# Protoshield_V1_0.net
KiCad netlist of a schematic drawn in EAGLE
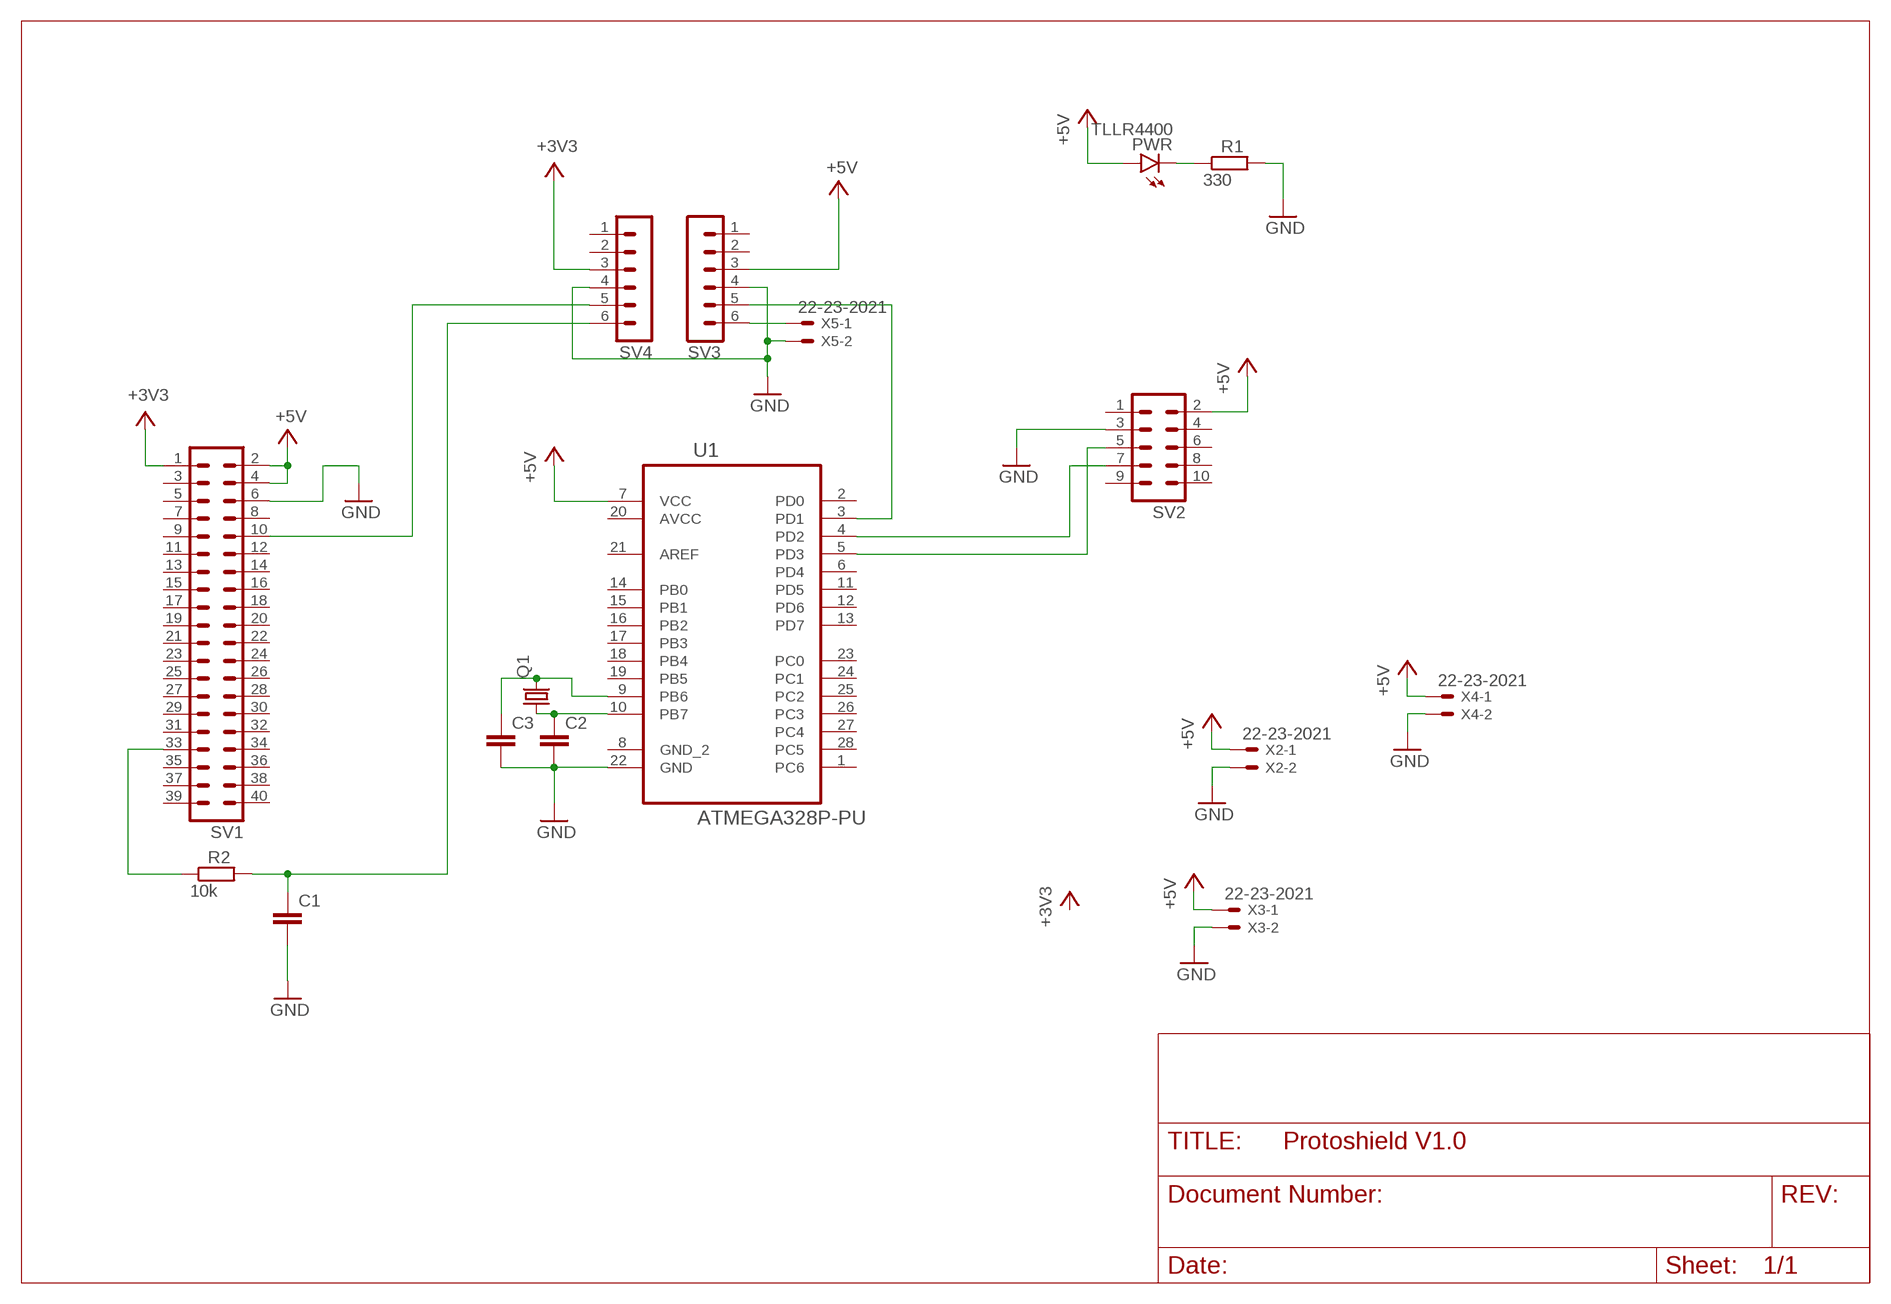
[diagram p0: schematic, sheet 1]

(export (version "E")
  (design (tool "Eeschema 10.0.6"))
  (components
    (comp (ref "C1")
      (value "C-EU050-024X044")
      (footprint "eagle-import:C050-024X044")
      (libsource (lib "eagle-import") (part "C-EU050-024X044"))
    )
    (comp (ref "C2")
      (value "C-EU050-024X044")
      (footprint "eagle-import:C050-024X044")
      (libsource (lib "eagle-import") (part "C-EU050-024X044"))
    )
    (comp (ref "C3")
      (value "C-EU050-024X044")
      (footprint "eagle-import:C050-024X044")
      (libsource (lib "eagle-import") (part "C-EU050-024X044"))
    )
    (comp (ref "PWR")
      (value "TLLR4400")
      (footprint "eagle-import:LED3MM")
      (fields (field (name "MF") "VISHAY SEMICONDUCTOR"))
      (libsource (lib "eagle-import") (part "TLLR4400"))
    )
    (comp (ref "Q1")
      (value "CRYSTALHC49S")
      (footprint "eagle-import:HC49_S")
      (libsource (lib "eagle-import") (part "CRYSTALHC49S"))
    )
    (comp (ref "R1")
      (value "330")
      (footprint "eagle-import:0207_7")
      (libsource (lib "eagle-import") (part "R-EU_0207/7"))
    )
    (comp (ref "R2")
      (value "10k")
      (footprint "eagle-import:0207_7")
      (libsource (lib "eagle-import") (part "R-EU_0207/7"))
    )
    (comp (ref "SV1")
      (value "MA20-2")
      (footprint "eagle-import:MA20-2")
      (libsource (lib "eagle-import") (part "MA20-2"))
    )
    (comp (ref "SV2")
      (value "MA05-2")
      (footprint "eagle-import:MA05-2")
      (libsource (lib "eagle-import") (part "MA05-2"))
    )
    (comp (ref "SV3")
      (value "MA06-1")
      (footprint "eagle-import:MA06-1")
      (libsource (lib "eagle-import") (part "MA06-1"))
    )
    (comp (ref "SV4")
      (value "MA06-1")
      (footprint "eagle-import:MA06-1")
      (libsource (lib "eagle-import") (part "MA06-1"))
    )
    (comp (ref "U1")
      (value "ATMEGA328P-PU")
      (footprint "eagle-import:DIP254P762X457-28")
      (libsource (lib "eagle-import") (part "ATMEGA328P-PU"))
    )
    (comp (ref "X2")
      (value "22-23-2021")
      (footprint "eagle-import:22-23-2021")
      (fields (field (name "MF") "MOLEX"))
      (libsource (lib "eagle-import") (part "22-23-2021"))
    )
    (comp (ref "X3")
      (value "22-23-2021")
      (footprint "eagle-import:22-23-2021")
      (fields (field (name "MF") "MOLEX"))
      (libsource (lib "eagle-import") (part "22-23-2021"))
    )
    (comp (ref "X4")
      (value "22-23-2021")
      (footprint "eagle-import:22-23-2021")
      (fields (field (name "MF") "MOLEX"))
      (libsource (lib "eagle-import") (part "22-23-2021"))
    )
    (comp (ref "X5")
      (value "22-23-2021")
      (footprint "eagle-import:22-23-2021")
      (fields (field (name "MF") "MOLEX"))
      (libsource (lib "eagle-import") (part "22-23-2021"))
    )
  )
  (nets
    (net (code "1") (name "+3V3") (class "Default")
      (node (ref "SV1") (pin "1") (pinfunction "1_1") (pintype "passive"))
      (node (ref "SV4") (pin "3") (pinfunction "3_3") (pintype "passive"))
    )
    (net (code "2") (name "+5V") (class "Default")
      (node (ref "PWR") (pin "A") (pinfunction "A_A") (pintype "passive"))
      (node (ref "SV1") (pin "2") (pinfunction "2_2") (pintype "passive"))
      (node (ref "SV1") (pin "4") (pinfunction "4_4") (pintype "passive"))
      (node (ref "SV2") (pin "2") (pinfunction "2_2") (pintype "passive"))
      (node (ref "SV3") (pin "3") (pinfunction "3_3") (pintype "passive"))
      (node (ref "U1") (pin "7") (pinfunction "VCC_7") (pintype "power_in"))
      (node (ref "X2") (pin "1") (pinfunction "S_1") (pintype "passive"))
      (node (ref "X3") (pin "1") (pinfunction "S_1") (pintype "passive"))
      (node (ref "X4") (pin "1") (pinfunction "S_1") (pintype "passive"))
    )
    (net (code "3") (name "/AVCC") (class "Default")
      (node (ref "U1") (pin "20") (pinfunction "AVCC_20") (pintype "power_in"))
    )
    (net (code "4") (name "GND") (class "Default")
      (node (ref "C1") (pin "2") (pinfunction "2_2") (pintype "passive"))
      (node (ref "C2") (pin "2") (pinfunction "2_2") (pintype "passive"))
      (node (ref "C3") (pin "2") (pinfunction "2_2") (pintype "passive"))
      (node (ref "R1") (pin "2") (pinfunction "2_2") (pintype "passive"))
      (node (ref "SV1") (pin "6") (pinfunction "6_6") (pintype "passive"))
      (node (ref "SV2") (pin "3") (pinfunction "3_3") (pintype "passive"))
      (node (ref "SV3") (pin "4") (pinfunction "4_4") (pintype "passive"))
      (node (ref "SV4") (pin "4") (pinfunction "4_4") (pintype "passive"))
      (node (ref "U1") (pin "22") (pinfunction "GND_22") (pintype "passive"))
      (node (ref "X2") (pin "2") (pinfunction "S_2") (pintype "passive"))
      (node (ref "X3") (pin "2") (pinfunction "S_2") (pintype "passive"))
      (node (ref "X4") (pin "2") (pinfunction "S_2") (pintype "passive"))
      (node (ref "X5") (pin "2") (pinfunction "S_2") (pintype "passive"))
    )
    (net (code "5") (name "Net-(C1-Pad1)") (class "Default")
      (node (ref "C1") (pin "1") (pinfunction "1_1") (pintype "passive"))
      (node (ref "R2") (pin "2") (pinfunction "2_2") (pintype "passive"))
      (node (ref "SV4") (pin "6") (pinfunction "6_6") (pintype "passive"))
    )
    (net (code "6") (name "Net-(PWR-C)") (class "Default")
      (node (ref "PWR") (pin "K") (pinfunction "C_K") (pintype "passive"))
      (node (ref "R1") (pin "1") (pinfunction "1_1") (pintype "passive"))
    )
    (net (code "7") (name "Net-(R2-Pad1)") (class "Default")
      (node (ref "R2") (pin "1") (pinfunction "1_1") (pintype "passive"))
      (node (ref "SV1") (pin "33") (pinfunction "33_33") (pintype "passive"))
    )
    (net (code "8") (name "Net-(SV1-Pad10)") (class "Default")
      (node (ref "SV1") (pin "10") (pinfunction "10_10") (pintype "passive"))
      (node (ref "SV4") (pin "5") (pinfunction "5_5") (pintype "passive"))
    )
    (net (code "9") (name "Net-(U1-PB6)") (class "Default")
      (node (ref "C3") (pin "1") (pinfunction "1_1") (pintype "passive"))
      (node (ref "Q1") (pin "2") (pinfunction "2_2") (pintype "passive"))
      (node (ref "U1") (pin "9") (pinfunction "PB6_9") (pintype "bidirectional"))
    )
    (net (code "10") (name "Net-(U1-PB7)") (class "Default")
      (node (ref "C2") (pin "1") (pinfunction "1_1") (pintype "passive"))
      (node (ref "Q1") (pin "1") (pinfunction "1_1") (pintype "passive"))
      (node (ref "U1") (pin "10") (pinfunction "PB7_10") (pintype "bidirectional"))
    )
    (net (code "11") (name "Net-(U1-PD1)") (class "Default")
      (node (ref "SV3") (pin "5") (pinfunction "5_5") (pintype "passive"))
      (node (ref "U1") (pin "3") (pinfunction "PD1_3") (pintype "bidirectional"))
    )
    (net (code "12") (name "Net-(U1-PD2)") (class "Default")
      (node (ref "SV2") (pin "7") (pinfunction "7_7") (pintype "passive"))
      (node (ref "U1") (pin "4") (pinfunction "PD2_4") (pintype "bidirectional"))
    )
    (net (code "13") (name "Net-(U1-PD3)") (class "Default")
      (node (ref "SV2") (pin "5") (pinfunction "5_5") (pintype "passive"))
      (node (ref "U1") (pin "5") (pinfunction "PD3_5") (pintype "bidirectional"))
    )
    (net (code "14") (name "Net-(X5A-S)") (class "Default")
      (node (ref "SV3") (pin "6") (pinfunction "6_6") (pintype "passive"))
      (node (ref "X5") (pin "1") (pinfunction "S_1") (pintype "passive"))
    )
    (net (code "15") (name "unconnected-(SV1-Pad3)") (class "Default")
      (node (ref "SV1") (pin "3") (pinfunction "3_3") (pintype "passive"))
    )
    (net (code "16") (name "unconnected-(SV1-Pad5)") (class "Default")
      (node (ref "SV1") (pin "5") (pinfunction "5_5") (pintype "passive"))
    )
    (net (code "17") (name "unconnected-(SV1-Pad7)") (class "Default")
      (node (ref "SV1") (pin "7") (pinfunction "7_7") (pintype "passive"))
    )
    (net (code "18") (name "unconnected-(SV1-Pad8)") (class "Default")
      (node (ref "SV1") (pin "8") (pinfunction "8_8") (pintype "passive"))
    )
    (net (code "19") (name "unconnected-(SV1-Pad9)") (class "Default")
      (node (ref "SV1") (pin "9") (pinfunction "9_9") (pintype "passive"))
    )
    (net (code "20") (name "unconnected-(SV1-Pad11)") (class "Default")
      (node (ref "SV1") (pin "11") (pinfunction "11_11") (pintype "passive"))
    )
    (net (code "21") (name "unconnected-(SV1-Pad12)") (class "Default")
      (node (ref "SV1") (pin "12") (pinfunction "12_12") (pintype "passive"))
    )
    (net (code "22") (name "unconnected-(SV1-Pad13)") (class "Default")
      (node (ref "SV1") (pin "13") (pinfunction "13_13") (pintype "passive"))
    )
    (net (code "23") (name "unconnected-(SV1-Pad14)") (class "Default")
      (node (ref "SV1") (pin "14") (pinfunction "14_14") (pintype "passive"))
    )
    (net (code "24") (name "unconnected-(SV1-Pad15)") (class "Default")
      (node (ref "SV1") (pin "15") (pinfunction "15_15") (pintype "passive"))
    )
    (net (code "25") (name "unconnected-(SV1-Pad16)") (class "Default")
      (node (ref "SV1") (pin "16") (pinfunction "16_16") (pintype "passive"))
    )
    (net (code "26") (name "unconnected-(SV1-Pad17)") (class "Default")
      (node (ref "SV1") (pin "17") (pinfunction "17_17") (pintype "passive"))
    )
    (net (code "27") (name "unconnected-(SV1-Pad18)") (class "Default")
      (node (ref "SV1") (pin "18") (pinfunction "18_18") (pintype "passive"))
    )
    (net (code "28") (name "unconnected-(SV1-Pad19)") (class "Default")
      (node (ref "SV1") (pin "19") (pinfunction "19_19") (pintype "passive"))
    )
    (net (code "29") (name "unconnected-(SV1-Pad20)") (class "Default")
      (node (ref "SV1") (pin "20") (pinfunction "20_20") (pintype "passive"))
    )
    (net (code "30") (name "unconnected-(SV1-Pad21)") (class "Default")
      (node (ref "SV1") (pin "21") (pinfunction "21_21") (pintype "passive"))
    )
    (net (code "31") (name "unconnected-(SV1-Pad22)") (class "Default")
      (node (ref "SV1") (pin "22") (pinfunction "22_22") (pintype "passive"))
    )
    (net (code "32") (name "unconnected-(SV1-Pad23)") (class "Default")
      (node (ref "SV1") (pin "23") (pinfunction "23_23") (pintype "passive"))
    )
    (net (code "33") (name "unconnected-(SV1-Pad24)") (class "Default")
      (node (ref "SV1") (pin "24") (pinfunction "24_24") (pintype "passive"))
    )
    (net (code "34") (name "unconnected-(SV1-Pad25)") (class "Default")
      (node (ref "SV1") (pin "25") (pinfunction "25_25") (pintype "passive"))
    )
    (net (code "35") (name "unconnected-(SV1-Pad26)") (class "Default")
      (node (ref "SV1") (pin "26") (pinfunction "26_26") (pintype "passive"))
    )
    (net (code "36") (name "unconnected-(SV1-Pad27)") (class "Default")
      (node (ref "SV1") (pin "27") (pinfunction "27_27") (pintype "passive"))
    )
    (net (code "37") (name "unconnected-(SV1-Pad28)") (class "Default")
      (node (ref "SV1") (pin "28") (pinfunction "28_28") (pintype "passive"))
    )
    (net (code "38") (name "unconnected-(SV1-Pad29)") (class "Default")
      (node (ref "SV1") (pin "29") (pinfunction "29_29") (pintype "passive"))
    )
    (net (code "39") (name "unconnected-(SV1-Pad30)") (class "Default")
      (node (ref "SV1") (pin "30") (pinfunction "30_30") (pintype "passive"))
    )
    (net (code "40") (name "unconnected-(SV1-Pad31)") (class "Default")
      (node (ref "SV1") (pin "31") (pinfunction "31_31") (pintype "passive"))
    )
    (net (code "41") (name "unconnected-(SV1-Pad32)") (class "Default")
      (node (ref "SV1") (pin "32") (pinfunction "32_32") (pintype "passive"))
    )
    (net (code "42") (name "unconnected-(SV1-Pad34)") (class "Default")
      (node (ref "SV1") (pin "34") (pinfunction "34_34") (pintype "passive"))
    )
    (net (code "43") (name "unconnected-(SV1-Pad35)") (class "Default")
      (node (ref "SV1") (pin "35") (pinfunction "35_35") (pintype "passive"))
    )
    (net (code "44") (name "unconnected-(SV1-Pad36)") (class "Default")
      (node (ref "SV1") (pin "36") (pinfunction "36_36") (pintype "passive"))
    )
    (net (code "45") (name "unconnected-(SV1-Pad37)") (class "Default")
      (node (ref "SV1") (pin "37") (pinfunction "37_37") (pintype "passive"))
    )
    (net (code "46") (name "unconnected-(SV1-Pad38)") (class "Default")
      (node (ref "SV1") (pin "38") (pinfunction "38_38") (pintype "passive"))
    )
    (net (code "47") (name "unconnected-(SV1-Pad39)") (class "Default")
      (node (ref "SV1") (pin "39") (pinfunction "39_39") (pintype "passive"))
    )
    (net (code "48") (name "unconnected-(SV1-Pad40)") (class "Default")
      (node (ref "SV1") (pin "40") (pinfunction "40_40") (pintype "passive"))
    )
    (net (code "49") (name "unconnected-(SV2-Pad1)") (class "Default")
      (node (ref "SV2") (pin "1") (pinfunction "1_1") (pintype "passive"))
    )
    (net (code "50") (name "unconnected-(SV2-Pad4)") (class "Default")
      (node (ref "SV2") (pin "4") (pinfunction "4_4") (pintype "passive"))
    )
    (net (code "51") (name "unconnected-(SV2-Pad6)") (class "Default")
      (node (ref "SV2") (pin "6") (pinfunction "6_6") (pintype "passive"))
    )
    (net (code "52") (name "unconnected-(SV2-Pad8)") (class "Default")
      (node (ref "SV2") (pin "8") (pinfunction "8_8") (pintype "passive"))
    )
    (net (code "53") (name "unconnected-(SV2-Pad9)") (class "Default")
      (node (ref "SV2") (pin "9") (pinfunction "9_9") (pintype "passive"))
    )
    (net (code "54") (name "unconnected-(SV2-Pad10)") (class "Default")
      (node (ref "SV2") (pin "10") (pinfunction "10_10") (pintype "passive"))
    )
    (net (code "55") (name "unconnected-(SV3-Pad1)") (class "Default")
      (node (ref "SV3") (pin "1") (pinfunction "1_1") (pintype "passive"))
    )
    (net (code "56") (name "unconnected-(SV3-Pad2)") (class "Default")
      (node (ref "SV3") (pin "2") (pinfunction "2_2") (pintype "passive"))
    )
    (net (code "57") (name "unconnected-(SV4-Pad1)") (class "Default")
      (node (ref "SV4") (pin "1") (pinfunction "1_1") (pintype "passive"))
    )
    (net (code "58") (name "unconnected-(SV4-Pad2)") (class "Default")
      (node (ref "SV4") (pin "2") (pinfunction "2_2") (pintype "passive"))
    )
    (net (code "59") (name "unconnected-(U1-AREF-Pad21)") (class "Default")
      (node (ref "U1") (pin "21") (pinfunction "AREF_21") (pintype "input"))
    )
    (net (code "60") (name "unconnected-(U1-GND_2-Pad8)") (class "Default")
      (node (ref "U1") (pin "8") (pinfunction "GND_2_8") (pintype "passive"))
    )
    (net (code "61") (name "unconnected-(U1-PB0-Pad14)") (class "Default")
      (node (ref "U1") (pin "14") (pinfunction "PB0_14") (pintype "bidirectional"))
    )
    (net (code "62") (name "unconnected-(U1-PB1-Pad15)") (class "Default")
      (node (ref "U1") (pin "15") (pinfunction "PB1_15") (pintype "bidirectional"))
    )
    (net (code "63") (name "unconnected-(U1-PB2-Pad16)") (class "Default")
      (node (ref "U1") (pin "16") (pinfunction "PB2_16") (pintype "bidirectional"))
    )
    (net (code "64") (name "unconnected-(U1-PB3-Pad17)") (class "Default")
      (node (ref "U1") (pin "17") (pinfunction "PB3_17") (pintype "bidirectional"))
    )
    (net (code "65") (name "unconnected-(U1-PB4-Pad18)") (class "Default")
      (node (ref "U1") (pin "18") (pinfunction "PB4_18") (pintype "bidirectional"))
    )
    (net (code "66") (name "unconnected-(U1-PB5-Pad19)") (class "Default")
      (node (ref "U1") (pin "19") (pinfunction "PB5_19") (pintype "bidirectional"))
    )
    (net (code "67") (name "unconnected-(U1-PC0-Pad23)") (class "Default")
      (node (ref "U1") (pin "23") (pinfunction "PC0_23") (pintype "bidirectional"))
    )
    (net (code "68") (name "unconnected-(U1-PC1-Pad24)") (class "Default")
      (node (ref "U1") (pin "24") (pinfunction "PC1_24") (pintype "bidirectional"))
    )
    (net (code "69") (name "unconnected-(U1-PC2-Pad25)") (class "Default")
      (node (ref "U1") (pin "25") (pinfunction "PC2_25") (pintype "bidirectional"))
    )
    (net (code "70") (name "unconnected-(U1-PC3-Pad26)") (class "Default")
      (node (ref "U1") (pin "26") (pinfunction "PC3_26") (pintype "bidirectional"))
    )
    (net (code "71") (name "unconnected-(U1-PC4-Pad27)") (class "Default")
      (node (ref "U1") (pin "27") (pinfunction "PC4_27") (pintype "bidirectional"))
    )
    (net (code "72") (name "unconnected-(U1-PC5-Pad28)") (class "Default")
      (node (ref "U1") (pin "28") (pinfunction "PC5_28") (pintype "bidirectional"))
    )
    (net (code "73") (name "unconnected-(U1-PC6-Pad1)") (class "Default")
      (node (ref "U1") (pin "1") (pinfunction "PC6_1") (pintype "bidirectional"))
    )
    (net (code "74") (name "unconnected-(U1-PD0-Pad2)") (class "Default")
      (node (ref "U1") (pin "2") (pinfunction "PD0_2") (pintype "bidirectional"))
    )
    (net (code "75") (name "unconnected-(U1-PD4-Pad6)") (class "Default")
      (node (ref "U1") (pin "6") (pinfunction "PD4_6") (pintype "bidirectional"))
    )
    (net (code "76") (name "unconnected-(U1-PD5-Pad11)") (class "Default")
      (node (ref "U1") (pin "11") (pinfunction "PD5_11") (pintype "bidirectional"))
    )
    (net (code "77") (name "unconnected-(U1-PD6-Pad12)") (class "Default")
      (node (ref "U1") (pin "12") (pinfunction "PD6_12") (pintype "bidirectional"))
    )
    (net (code "78") (name "unconnected-(U1-PD7-Pad13)") (class "Default")
      (node (ref "U1") (pin "13") (pinfunction "PD7_13") (pintype "bidirectional"))
    )
  )
)
